# Pure_Keys_aec-pcb3.net
KiCad netlist of a schematic drawn in EAGLE
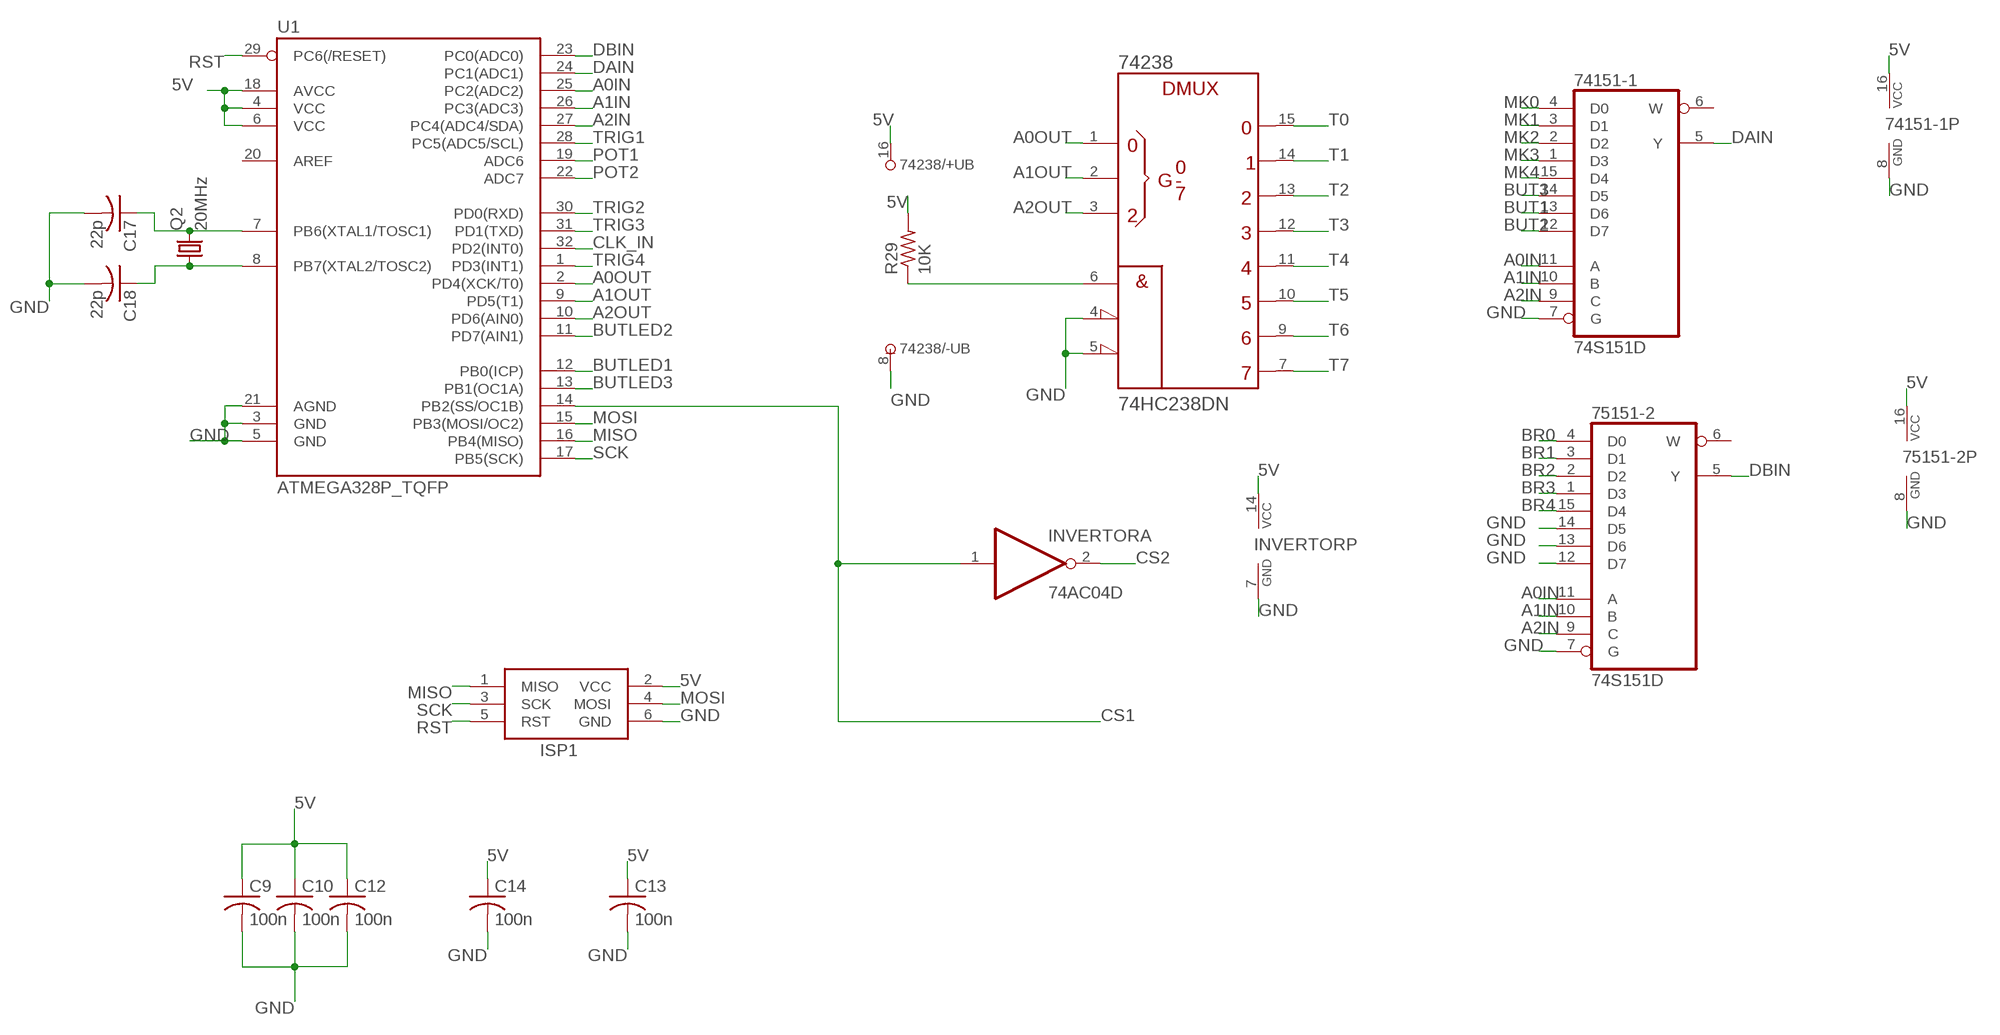
[diagram p0: schematic, sheet 1]
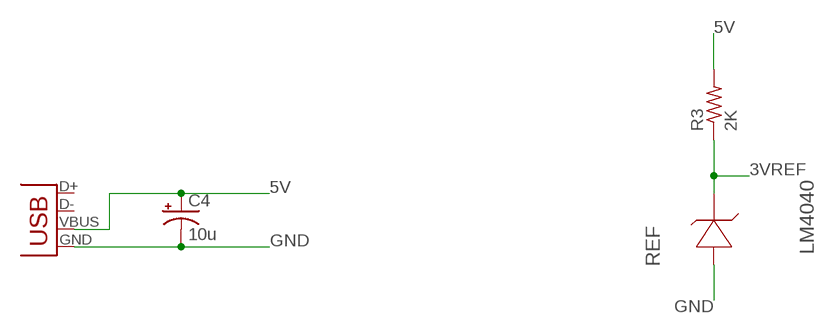
[diagram p1: schematic, sheet 2]
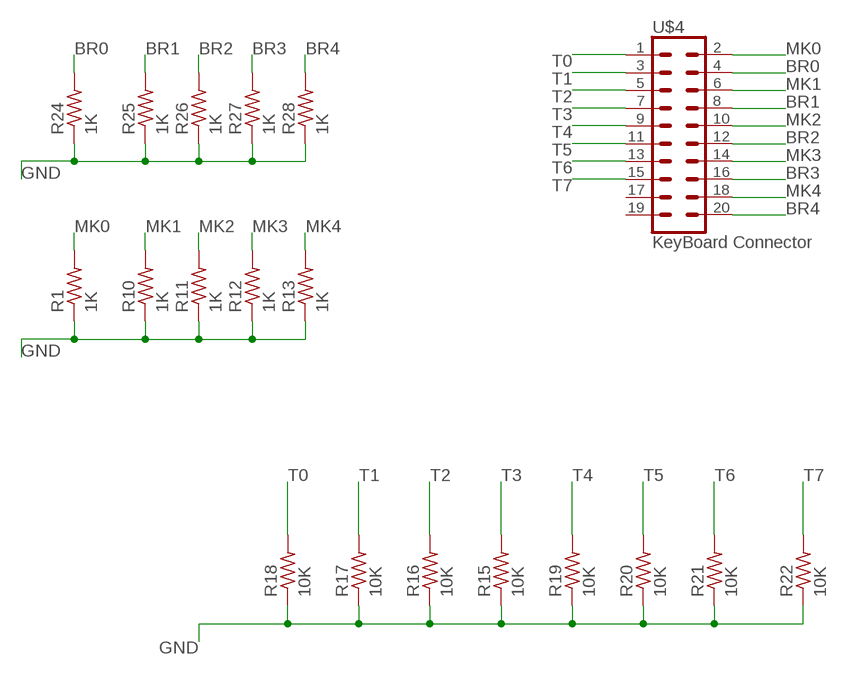
[diagram p2: schematic, sheet 3]
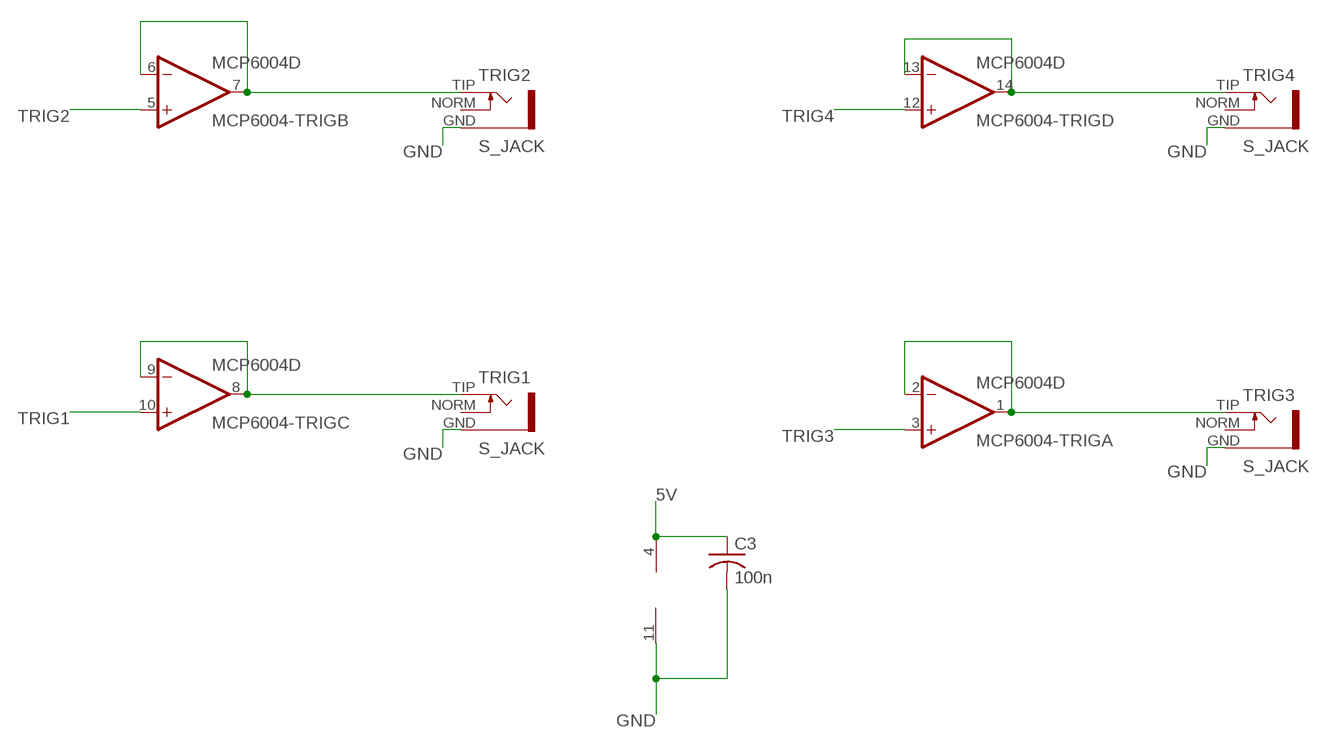
[diagram p3: schematic, sheet 4]
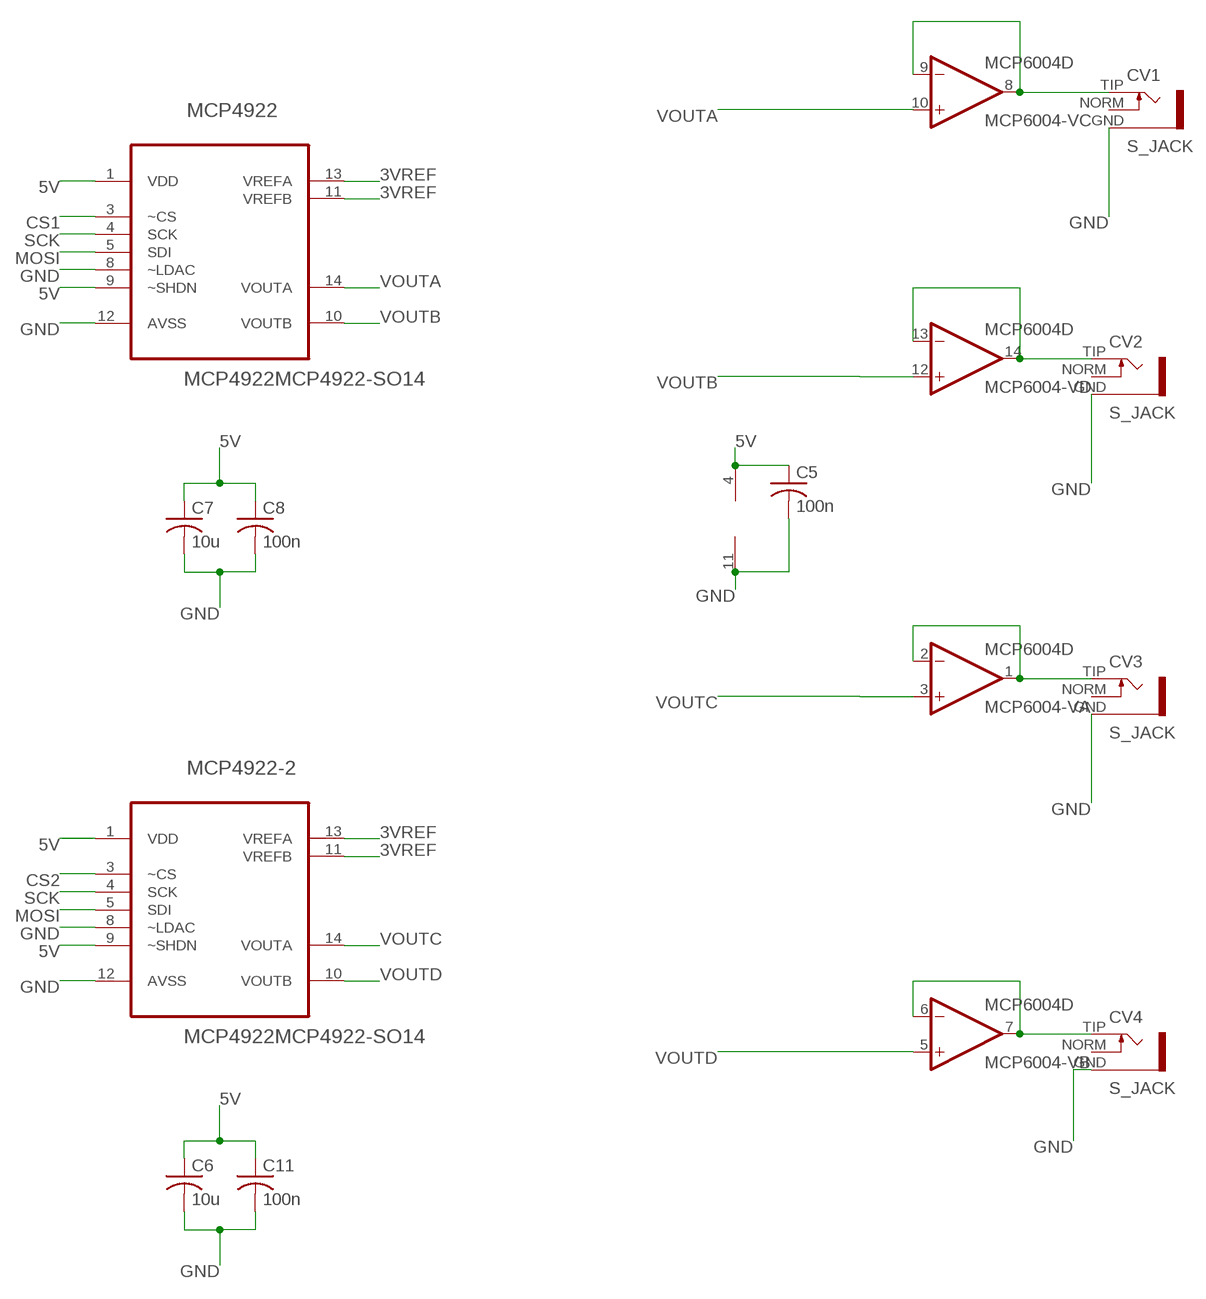
[diagram p4: schematic, sheet 5]
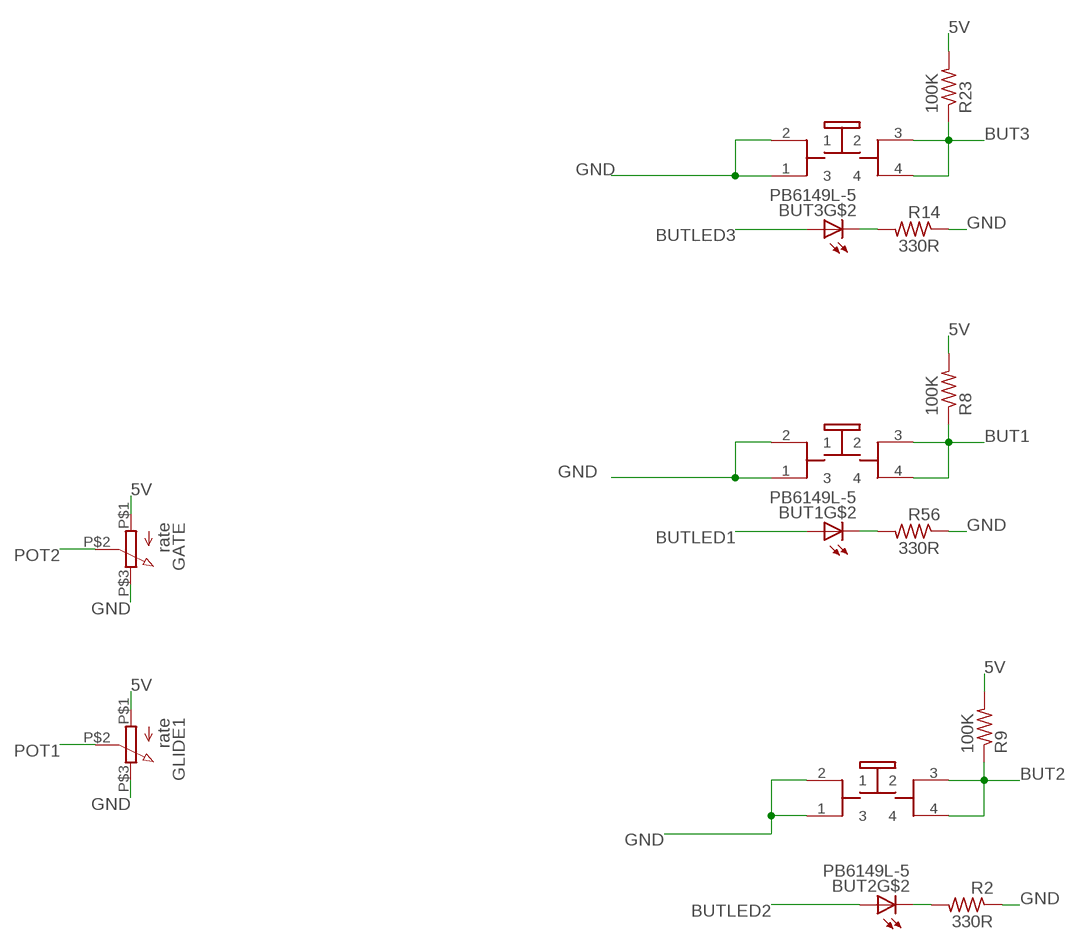
[diagram p5: schematic, sheet 6]
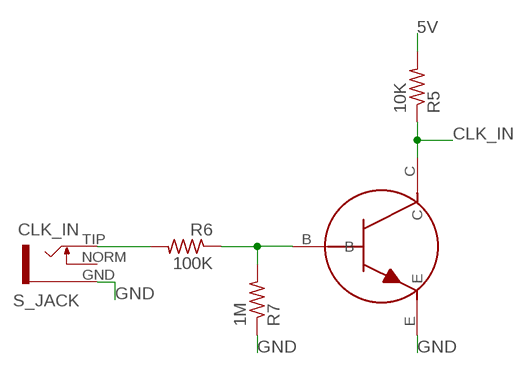
[diagram p6: schematic, sheet 7]

(export (version "E")
  (design (tool "Eeschema 10.0.6"))
  (components
    (comp (ref "CLK_IN")
      (value "S_JACK")
      (footprint "eagle-import:S_JACK")
      (libsource (lib "eagle-import") (part "S_JACK"))
    )
    (comp (ref "CLOCK")
      (value "2N3904")
      (footprint "eagle-import:TRANSISTOR_SINGLE_N-TYPE")
      (fields (field (name "RS-PART") "725-8616 "))
      (libsource (lib "eagle-import") (part "TRANSISTOR_MMBT3904"))
    )
    (comp (ref "R5")
      (value "10K")
      (footprint "eagle-import:R0805")
      (libsource (lib "eagle-import") (part "R-US_R0805"))
    )
    (comp (ref "R6")
      (value "100K")
      (footprint "eagle-import:R0805")
      (libsource (lib "eagle-import") (part "R-US_R0805"))
    )
    (comp (ref "R7")
      (value "1M")
      (footprint "eagle-import:R0805")
      (libsource (lib "eagle-import") (part "R-US_R0805"))
    )
    (comp (ref "74151-1")
      (value "74S151D")
      (footprint "eagle-import:SO16")
      (fields (field (name "RS-PART") "436-7436"))
      (libsource (lib "eagle-import") (part "74151DS"))
    )
    (comp (ref "74238")
      (value "74HC238DN")
      (footprint "eagle-import:SO16")
      (fields (field (name "RS-PART") "483-6487 (10off)"))
      (libsource (lib "eagle-import") (part "74HC238DN"))
    )
    (comp (ref "75151-2")
      (value "74S151D")
      (footprint "eagle-import:SO16")
      (fields (field (name "RS-PART") "436-7436"))
      (libsource (lib "eagle-import") (part "74151DS"))
    )
    (comp (ref "C9")
      (value "100n")
      (footprint "eagle-import:C0805K")
      (libsource (lib "eagle-import") (part "C-USC0805K"))
    )
    (comp (ref "C10")
      (value "100n")
      (footprint "eagle-import:C0805K")
      (libsource (lib "eagle-import") (part "C-USC0805K"))
    )
    (comp (ref "C12")
      (value "100n")
      (footprint "eagle-import:C0805K")
      (libsource (lib "eagle-import") (part "C-USC0805K"))
    )
    (comp (ref "C13")
      (value "100n")
      (footprint "eagle-import:C0805K")
      (libsource (lib "eagle-import") (part "C-USC0805K"))
    )
    (comp (ref "C14")
      (value "100n")
      (footprint "eagle-import:C0805K")
      (libsource (lib "eagle-import") (part "C-USC0805K"))
    )
    (comp (ref "C17")
      (value "22p")
      (footprint "eagle-import:C0805K")
      (libsource (lib "eagle-import") (part "C-USC0805K"))
    )
    (comp (ref "C18")
      (value "22p")
      (footprint "eagle-import:C0805K")
      (libsource (lib "eagle-import") (part "C-USC0805K"))
    )
    (comp (ref "INVERTOR")
      (value "74AC04D")
      (footprint "eagle-import:SO14")
      (fields (field (name "RS-PART") "171-3461 (50 off)"))
      (libsource (lib "eagle-import") (part "7404DAC"))
    )
    (comp (ref "ISP1")
      (value "AVRISP-6")
      (footprint "eagle-import:AVRISP")
      (libsource (lib "eagle-import") (part "AVRISP-6"))
    )
    (comp (ref "Q2")
      (value "20MHz")
      (footprint "eagle-import:HC49UP")
      (libsource (lib "eagle-import") (part "CRYSTALHC49UP"))
    )
    (comp (ref "R29")
      (value "10K")
      (footprint "eagle-import:R0805")
      (libsource (lib "eagle-import") (part "R-US_R0805"))
    )
    (comp (ref "U1")
      (value "ATMEGA328P_TQFP")
      (footprint "eagle-import:TQFP32-08")
      (fields (field (name "RS-PART") "131-0271"))
      (libsource (lib "eagle-import") (part "ATMEGA328P_TQFP"))
    )
    (comp (ref "C3")
      (value "100n")
      (footprint "eagle-import:C0805K")
      (libsource (lib "eagle-import") (part "C-USC0805K"))
    )
    (comp (ref "MCP6004-TRIG")
      (value "MCP6004D")
      (footprint "eagle-import:SO14")
      (fields (field (name "RS-PART") "628-3481 (10)"))
      (libsource (lib "eagle-import") (part "MCP6004D"))
    )
    (comp (ref "TRIG1")
      (value "S_JACK")
      (footprint "eagle-import:S_JACK")
      (libsource (lib "eagle-import") (part "S_JACK"))
    )
    (comp (ref "TRIG2")
      (value "S_JACK")
      (footprint "eagle-import:S_JACK")
      (libsource (lib "eagle-import") (part "S_JACK"))
    )
    (comp (ref "TRIG3")
      (value "S_JACK")
      (footprint "eagle-import:S_JACK")
      (libsource (lib "eagle-import") (part "S_JACK"))
    )
    (comp (ref "TRIG4")
      (value "S_JACK")
      (footprint "eagle-import:S_JACK")
      (libsource (lib "eagle-import") (part "S_JACK"))
    )
    (comp (ref "C5")
      (value "100n")
      (footprint "eagle-import:C0805K")
      (libsource (lib "eagle-import") (part "C-USC0805K"))
    )
    (comp (ref "C6")
      (value "10u")
      (footprint "eagle-import:C0805K")
      (libsource (lib "eagle-import") (part "C-USC0805K"))
    )
    (comp (ref "C7")
      (value "10u")
      (footprint "eagle-import:C0805K")
      (libsource (lib "eagle-import") (part "C-USC0805K"))
    )
    (comp (ref "C8")
      (value "100n")
      (footprint "eagle-import:C0805K")
      (libsource (lib "eagle-import") (part "C-USC0805K"))
    )
    (comp (ref "C11")
      (value "100n")
      (footprint "eagle-import:C0805K")
      (libsource (lib "eagle-import") (part "C-USC0805K"))
    )
    (comp (ref "CV1")
      (value "S_JACK")
      (footprint "eagle-import:S_JACK")
      (libsource (lib "eagle-import") (part "S_JACK"))
    )
    (comp (ref "CV2")
      (value "S_JACK")
      (footprint "eagle-import:S_JACK")
      (libsource (lib "eagle-import") (part "S_JACK"))
    )
    (comp (ref "CV3")
      (value "S_JACK")
      (footprint "eagle-import:S_JACK")
      (libsource (lib "eagle-import") (part "S_JACK"))
    )
    (comp (ref "CV4")
      (value "S_JACK")
      (footprint "eagle-import:S_JACK")
      (libsource (lib "eagle-import") (part "S_JACK"))
    )
    (comp (ref "MCP4922")
      (value "MCP4922MCP4922-SO14")
      (footprint "eagle-import:SO14")
      (fields (field (name "RS-PART") "402-910 "))
      (libsource (lib "eagle-import") (part "MCP4922MCP4922-SO14"))
    )
    (comp (ref "MCP4922-2")
      (value "MCP4922MCP4922-SO14")
      (footprint "eagle-import:SO14")
      (libsource (lib "eagle-import") (part "MCP4922MCP4922-SO14"))
    )
    (comp (ref "MCP6004-V")
      (value "MCP6004D")
      (footprint "eagle-import:SO14")
      (fields (field (name "RS-PART") "628-3481 (10)"))
      (libsource (lib "eagle-import") (part "MCP6004D"))
    )
    (comp (ref "R1")
      (value "1K")
      (footprint "eagle-import:R0805")
      (fields (field (name "RS-PART") "223-0427"))
      (libsource (lib "eagle-import") (part "R-US_R0805"))
    )
    (comp (ref "R10")
      (value "1K")
      (footprint "eagle-import:R0805")
      (fields (field (name "RS-PART") "223-0427"))
      (libsource (lib "eagle-import") (part "R-US_R0805"))
    )
    (comp (ref "R11")
      (value "1K")
      (footprint "eagle-import:R0805")
      (fields (field (name "RS-PART") "223-0427"))
      (libsource (lib "eagle-import") (part "R-US_R0805"))
    )
    (comp (ref "R12")
      (value "1K")
      (footprint "eagle-import:R0805")
      (fields (field (name "RS-PART") "223-0427"))
      (libsource (lib "eagle-import") (part "R-US_R0805"))
    )
    (comp (ref "R13")
      (value "1K")
      (footprint "eagle-import:R0805")
      (fields (field (name "RS-PART") "223-0427"))
      (libsource (lib "eagle-import") (part "R-US_R0805"))
    )
    (comp (ref "R15")
      (value "10K")
      (footprint "eagle-import:R0805")
      (libsource (lib "eagle-import") (part "R-US_R0805"))
    )
    (comp (ref "R16")
      (value "10K")
      (footprint "eagle-import:R0805")
      (libsource (lib "eagle-import") (part "R-US_R0805"))
    )
    (comp (ref "R17")
      (value "10K")
      (footprint "eagle-import:R0805")
      (libsource (lib "eagle-import") (part "R-US_R0805"))
    )
    (comp (ref "R18")
      (value "10K")
      (footprint "eagle-import:R0805")
      (libsource (lib "eagle-import") (part "R-US_R0805"))
    )
    (comp (ref "R19")
      (value "10K")
      (footprint "eagle-import:R0805")
      (libsource (lib "eagle-import") (part "R-US_R0805"))
    )
    (comp (ref "R20")
      (value "10K")
      (footprint "eagle-import:R0805")
      (libsource (lib "eagle-import") (part "R-US_R0805"))
    )
    (comp (ref "R21")
      (value "10K")
      (footprint "eagle-import:R0805")
      (libsource (lib "eagle-import") (part "R-US_R0805"))
    )
    (comp (ref "R22")
      (value "10K")
      (footprint "eagle-import:R0805")
      (libsource (lib "eagle-import") (part "R-US_R0805"))
    )
    (comp (ref "R24")
      (value "1K")
      (footprint "eagle-import:R0805")
      (fields (field (name "RS-PART") "223-0427"))
      (libsource (lib "eagle-import") (part "R-US_R0805"))
    )
    (comp (ref "R25")
      (value "1K")
      (footprint "eagle-import:R0805")
      (fields (field (name "RS-PART") "223-0427"))
      (libsource (lib "eagle-import") (part "R-US_R0805"))
    )
    (comp (ref "R26")
      (value "1K")
      (footprint "eagle-import:R0805")
      (fields (field (name "RS-PART") "223-0427"))
      (libsource (lib "eagle-import") (part "R-US_R0805"))
    )
    (comp (ref "R27")
      (value "1K")
      (footprint "eagle-import:R0805")
      (fields (field (name "RS-PART") "223-0427"))
      (libsource (lib "eagle-import") (part "R-US_R0805"))
    )
    (comp (ref "R28")
      (value "1K")
      (footprint "eagle-import:R0805")
      (fields (field (name "RS-PART") "223-0427"))
      (libsource (lib "eagle-import") (part "R-US_R0805"))
    )
    (comp (ref "U$4")
      (value "KeyBoard Connector")
      (footprint "eagle-import:2X10")
      (fields (field (name "RS-PART") "669-5364"))
      (libsource (lib "eagle-import") (part "CONN_10X2"))
    )
    (comp (ref "C4")
      (value "10u")
      (footprint "eagle-import:153CLV-0505")
      (libsource (lib "eagle-import") (part "CPOL-US153CLV-0505"))
    )
    (comp (ref "JP2")
      (value "USB-B")
      (footprint "eagle-import:USB-B-PTH")
      (libsource (lib "eagle-import") (part "USBPTH"))
    )
    (comp (ref "R3")
      (value "2K")
      (footprint "eagle-import:R0805")
      (libsource (lib "eagle-import") (part "R-US_R0805"))
    )
    (comp (ref "REF")
      (value "LM4040")
      (footprint "eagle-import:SOT95P237X112-3N")
      (fields
        (field (name "MPN") "LM4040A50IDBZT")
        (field (name "MPN_1") "LM4040A30IDBZT")
        (field (name "RS-PART") "809-6343")
      )
      (libsource (lib "eagle-import") (part "LM4040A30IDBZT"))
    )
    (comp (ref "BUT1")
      (value "PB6149L-5")
      (footprint "eagle-import:PB6149L")
      (libsource (lib "eagle-import") (part "PB6149L-5"))
    )
    (comp (ref "BUT2")
      (value "PB6149L-5")
      (footprint "eagle-import:PB6149L")
      (libsource (lib "eagle-import") (part "PB6149L-5"))
    )
    (comp (ref "BUT3")
      (value "PB6149L-5")
      (footprint "eagle-import:PB6149L")
      (libsource (lib "eagle-import") (part "PB6149L-5"))
    )
    (comp (ref "GATE")
      (value "rate")
      (footprint "eagle-import:POT")
      (libsource (lib "eagle-import") (part "9MMPOT"))
    )
    (comp (ref "GLIDE1")
      (value "rate")
      (footprint "eagle-import:POT")
      (libsource (lib "eagle-import") (part "9MMPOT"))
    )
    (comp (ref "R2")
      (value "330R")
      (footprint "eagle-import:R0805")
      (libsource (lib "eagle-import") (part "R-US_R0805"))
    )
    (comp (ref "R8")
      (value "100K")
      (footprint "eagle-import:R0805")
      (libsource (lib "eagle-import") (part "R-US_R0805"))
    )
    (comp (ref "R9")
      (value "100K")
      (footprint "eagle-import:R0805")
      (libsource (lib "eagle-import") (part "R-US_R0805"))
    )
    (comp (ref "R14")
      (value "330R")
      (footprint "eagle-import:R0805")
      (libsource (lib "eagle-import") (part "R-US_R0805"))
    )
    (comp (ref "R23")
      (value "100K")
      (footprint "eagle-import:R0805")
      (libsource (lib "eagle-import") (part "R-US_R0805"))
    )
    (comp (ref "R56")
      (value "330R")
      (footprint "eagle-import:R0805")
      (libsource (lib "eagle-import") (part "R-US_R0805"))
    )
  )
  (nets
    (net (code "1") (name "3VREF") (class "Default")
      (node (ref "MCP4922") (pin "11") (pinfunction "VREFB_11") (pintype "bidirectional"))
      (node (ref "MCP4922") (pin "13") (pinfunction "VREFA_13") (pintype "input"))
      (node (ref "MCP4922-2") (pin "11") (pinfunction "VREFB_11") (pintype "bidirectional"))
      (node (ref "MCP4922-2") (pin "13") (pinfunction "VREFA_13") (pintype "input"))
      (node (ref "R3") (pin "1") (pinfunction "1_1") (pintype "passive"))
      (node (ref "REF") (pin "1") (pinfunction "CATHODE_1") (pintype "output"))
    )
    (net (code "2") (name "5V") (class "Default")
      (node (ref "74151-1") (pin "16") (pinfunction "VCC_16") (pintype "power_in"))
      (node (ref "74238") (pin "16") (pinfunction "+UB_16") (pintype "power_in"))
      (node (ref "75151-2") (pin "16") (pinfunction "VCC_16") (pintype "power_in"))
      (node (ref "C10") (pin "1") (pinfunction "1_1") (pintype "passive"))
      (node (ref "C11") (pin "1") (pinfunction "1_1") (pintype "passive"))
      (node (ref "C12") (pin "1") (pinfunction "1_1") (pintype "passive"))
      (node (ref "C13") (pin "1") (pinfunction "1_1") (pintype "passive"))
      (node (ref "C14") (pin "1") (pinfunction "1_1") (pintype "passive"))
      (node (ref "C3") (pin "1") (pinfunction "1_1") (pintype "passive"))
      (node (ref "C4") (pin "+") (pinfunction "+_+") (pintype "passive"))
      (node (ref "C5") (pin "1") (pinfunction "1_1") (pintype "passive"))
      (node (ref "C6") (pin "1") (pinfunction "1_1") (pintype "passive"))
      (node (ref "C7") (pin "1") (pinfunction "1_1") (pintype "passive"))
      (node (ref "C8") (pin "1") (pinfunction "1_1") (pintype "passive"))
      (node (ref "C9") (pin "1") (pinfunction "1_1") (pintype "passive"))
      (node (ref "GATE") (pin "P$1") (pinfunction "1_P$1") (pintype "passive"))
      (node (ref "GLIDE1") (pin "P$1") (pinfunction "1_P$1") (pintype "passive"))
      (node (ref "INVERTOR") (pin "14") (pinfunction "VCC_14") (pintype "power_in"))
      (node (ref "ISP1") (pin "2") (pinfunction "VCC_2") (pintype "power_in"))
      (node (ref "JP2") (pin "VBUS") (pinfunction "VBUS_VBUS") (pintype "bidirectional"))
      (node (ref "MCP4922") (pin "1") (pinfunction "VDD_1") (pintype "power_in"))
      (node (ref "MCP4922") (pin "9") (pinfunction "~{SHDN}_9") (pintype "bidirectional"))
      (node (ref "MCP4922-2") (pin "1") (pinfunction "VDD_1") (pintype "power_in"))
      (node (ref "MCP4922-2") (pin "9") (pinfunction "~{SHDN}_9") (pintype "bidirectional"))
      (node (ref "MCP6004-TRIG") (pin "4") (pinfunction "V+_4") (pintype "power_in"))
      (node (ref "MCP6004-V") (pin "4") (pinfunction "V+_4") (pintype "power_in"))
      (node (ref "R23") (pin "2") (pinfunction "2_2") (pintype "passive"))
      (node (ref "R29") (pin "2") (pinfunction "2_2") (pintype "passive"))
      (node (ref "R3") (pin "2") (pinfunction "2_2") (pintype "passive"))
      (node (ref "R5") (pin "2") (pinfunction "2_2") (pintype "passive"))
      (node (ref "R8") (pin "2") (pinfunction "2_2") (pintype "passive"))
      (node (ref "R9") (pin "2") (pinfunction "2_2") (pintype "passive"))
      (node (ref "U1") (pin "18") (pinfunction "AVCC_18") (pintype "bidirectional"))
      (node (ref "U1") (pin "4") (pinfunction "VCC_4") (pintype "bidirectional"))
      (node (ref "U1") (pin "6") (pinfunction "VCC_6") (pintype "bidirectional"))
    )
    (net (code "3") (name "A0IN") (class "Default")
      (node (ref "74151-1") (pin "11") (pinfunction "A_11") (pintype "input"))
      (node (ref "75151-2") (pin "11") (pinfunction "A_11") (pintype "input"))
      (node (ref "U1") (pin "25") (pinfunction "PC2(ADC2)_25") (pintype "bidirectional"))
    )
    (net (code "4") (name "A0OUT") (class "Default")
      (node (ref "74238") (pin "1") (pinfunction "A_1") (pintype "input"))
      (node (ref "U1") (pin "2") (pinfunction "PD4(XCK/T0)_2") (pintype "bidirectional"))
    )
    (net (code "5") (name "A1IN") (class "Default")
      (node (ref "74151-1") (pin "10") (pinfunction "B_10") (pintype "input"))
      (node (ref "75151-2") (pin "10") (pinfunction "B_10") (pintype "input"))
      (node (ref "U1") (pin "26") (pinfunction "PC3(ADC3)_26") (pintype "bidirectional"))
    )
    (net (code "6") (name "A1OUT") (class "Default")
      (node (ref "74238") (pin "2") (pinfunction "B_2") (pintype "input"))
      (node (ref "U1") (pin "9") (pinfunction "PD5(T1)_9") (pintype "bidirectional"))
    )
    (net (code "7") (name "A2IN") (class "Default")
      (node (ref "74151-1") (pin "9") (pinfunction "C_9") (pintype "input"))
      (node (ref "75151-2") (pin "9") (pinfunction "C_9") (pintype "input"))
      (node (ref "U1") (pin "27") (pinfunction "PC4(ADC4/SDA)_27") (pintype "bidirectional"))
    )
    (net (code "8") (name "A2OUT") (class "Default")
      (node (ref "74238") (pin "3") (pinfunction "C_3") (pintype "input"))
      (node (ref "U1") (pin "10") (pinfunction "PD6(AIN0)_10") (pintype "bidirectional"))
    )
    (net (code "9") (name "BR0") (class "Default")
      (node (ref "75151-2") (pin "4") (pinfunction "D0_4") (pintype "input"))
      (node (ref "R24") (pin "2") (pinfunction "2_2") (pintype "passive"))
      (node (ref "U$4") (pin "4") (pinfunction "4_4") (pintype "passive"))
    )
    (net (code "10") (name "BR1") (class "Default")
      (node (ref "75151-2") (pin "3") (pinfunction "D1_3") (pintype "input"))
      (node (ref "R25") (pin "2") (pinfunction "2_2") (pintype "passive"))
      (node (ref "U$4") (pin "8") (pinfunction "8_8") (pintype "passive"))
    )
    (net (code "11") (name "BR2") (class "Default")
      (node (ref "75151-2") (pin "2") (pinfunction "D2_2") (pintype "input"))
      (node (ref "R26") (pin "2") (pinfunction "2_2") (pintype "passive"))
      (node (ref "U$4") (pin "12") (pinfunction "12_12") (pintype "passive"))
    )
    (net (code "12") (name "BR3") (class "Default")
      (node (ref "75151-2") (pin "1") (pinfunction "D3_1") (pintype "input"))
      (node (ref "R27") (pin "2") (pinfunction "2_2") (pintype "passive"))
      (node (ref "U$4") (pin "16") (pinfunction "16_16") (pintype "passive"))
    )
    (net (code "13") (name "BR4") (class "Default")
      (node (ref "75151-2") (pin "15") (pinfunction "D4_15") (pintype "input"))
      (node (ref "R28") (pin "2") (pinfunction "2_2") (pintype "passive"))
      (node (ref "U$4") (pin "20") (pinfunction "20_20") (pintype "passive"))
    )
    (net (code "14") (name "BUT1") (class "Default")
      (node (ref "74151-1") (pin "13") (pinfunction "D6_13") (pintype "input"))
      (node (ref "BUT1") (pin "3") (pinfunction "2_3") (pintype "bidirectional"))
      (node (ref "BUT1") (pin "4") (pinfunction "4_4") (pintype "bidirectional"))
      (node (ref "R8") (pin "1") (pinfunction "1_1") (pintype "passive"))
    )
    (net (code "15") (name "BUT2") (class "Default")
      (node (ref "74151-1") (pin "12") (pinfunction "D7_12") (pintype "input"))
      (node (ref "BUT2") (pin "3") (pinfunction "2_3") (pintype "bidirectional"))
      (node (ref "BUT2") (pin "4") (pinfunction "4_4") (pintype "bidirectional"))
      (node (ref "R9") (pin "1") (pinfunction "1_1") (pintype "passive"))
    )
    (net (code "16") (name "BUT3") (class "Default")
      (node (ref "74151-1") (pin "14") (pinfunction "D5_14") (pintype "input"))
      (node (ref "BUT3") (pin "3") (pinfunction "2_3") (pintype "bidirectional"))
      (node (ref "BUT3") (pin "4") (pinfunction "4_4") (pintype "bidirectional"))
      (node (ref "R23") (pin "1") (pinfunction "1_1") (pintype "passive"))
    )
    (net (code "17") (name "BUTLED1") (class "Default")
      (node (ref "BUT1") (pin "A") (pinfunction "A_A") (pintype "passive"))
      (node (ref "U1") (pin "12") (pinfunction "PB0(ICP)_12") (pintype "bidirectional"))
    )
    (net (code "18") (name "BUTLED2") (class "Default")
      (node (ref "BUT2") (pin "A") (pinfunction "A_A") (pintype "passive"))
      (node (ref "U1") (pin "11") (pinfunction "PD7(AIN1)_11") (pintype "bidirectional"))
    )
    (net (code "19") (name "BUTLED3") (class "Default")
      (node (ref "BUT3") (pin "A") (pinfunction "A_A") (pintype "passive"))
      (node (ref "U1") (pin "13") (pinfunction "PB1(OC1A)_13") (pintype "bidirectional"))
    )
    (net (code "20") (name "CLK_IN") (class "Default")
      (node (ref "CLOCK") (pin "C") (pinfunction "C_C") (pintype "bidirectional"))
      (node (ref "R5") (pin "1") (pinfunction "1_1") (pintype "passive"))
      (node (ref "U1") (pin "32") (pinfunction "PD2(INT0)_32") (pintype "bidirectional"))
    )
    (net (code "21") (name "CS1") (class "Default")
      (node (ref "INVERTOR") (pin "1") (pinfunction "I_1") (pintype "input"))
      (node (ref "MCP4922") (pin "3") (pinfunction "~{CS}_3") (pintype "input"))
      (node (ref "U1") (pin "14") (pinfunction "PB2(SS/OC1B)_14") (pintype "bidirectional"))
    )
    (net (code "22") (name "CS2") (class "Default")
      (node (ref "INVERTOR") (pin "2") (pinfunction "O_2") (pintype "output"))
      (node (ref "MCP4922-2") (pin "3") (pinfunction "~{CS}_3") (pintype "input"))
    )
    (net (code "23") (name "DAIN") (class "Default")
      (node (ref "74151-1") (pin "5") (pinfunction "Y_5") (pintype "output"))
      (node (ref "U1") (pin "24") (pinfunction "PC1(ADC1)_24") (pintype "bidirectional"))
    )
    (net (code "24") (name "DBIN") (class "Default")
      (node (ref "75151-2") (pin "5") (pinfunction "Y_5") (pintype "output"))
      (node (ref "U1") (pin "23") (pinfunction "PC0(ADC0)_23") (pintype "bidirectional"))
    )
    (net (code "25") (name "GND") (class "Default")
      (node (ref "74151-1") (pin "7") (pinfunction "G_7") (pintype "input"))
      (node (ref "74151-1") (pin "8") (pinfunction "GND_8") (pintype "power_in"))
      (node (ref "74238") (pin "4") (pinfunction "~{G2A}_4") (pintype "input"))
      (node (ref "74238") (pin "5") (pinfunction "~{G2B}_5") (pintype "input"))
      (node (ref "74238") (pin "8") (pinfunction "-UB_8") (pintype "power_in"))
      (node (ref "75151-2") (pin "12") (pinfunction "D7_12") (pintype "input"))
      (node (ref "75151-2") (pin "13") (pinfunction "D6_13") (pintype "input"))
      (node (ref "75151-2") (pin "14") (pinfunction "D5_14") (pintype "input"))
      (node (ref "75151-2") (pin "7") (pinfunction "G_7") (pintype "input"))
      (node (ref "75151-2") (pin "8") (pinfunction "GND_8") (pintype "power_in"))
      (node (ref "BUT1") (pin "1") (pinfunction "3_1") (pintype "bidirectional"))
      (node (ref "BUT1") (pin "2") (pinfunction "1_2") (pintype "bidirectional"))
      (node (ref "BUT2") (pin "1") (pinfunction "3_1") (pintype "bidirectional"))
      (node (ref "BUT2") (pin "2") (pinfunction "1_2") (pintype "bidirectional"))
      (node (ref "BUT3") (pin "1") (pinfunction "3_1") (pintype "bidirectional"))
      (node (ref "BUT3") (pin "2") (pinfunction "1_2") (pintype "bidirectional"))
      (node (ref "C10") (pin "2") (pinfunction "2_2") (pintype "passive"))
      (node (ref "C11") (pin "2") (pinfunction "2_2") (pintype "passive"))
      (node (ref "C12") (pin "2") (pinfunction "2_2") (pintype "passive"))
      (node (ref "C13") (pin "2") (pinfunction "2_2") (pintype "passive"))
      (node (ref "C14") (pin "2") (pinfunction "2_2") (pintype "passive"))
      (node (ref "C17") (pin "2") (pinfunction "2_2") (pintype "passive"))
      (node (ref "C18") (pin "2") (pinfunction "2_2") (pintype "passive"))
      (node (ref "C3") (pin "2") (pinfunction "2_2") (pintype "passive"))
      (node (ref "C4") (pin "-") (pinfunction "-_-") (pintype "passive"))
      (node (ref "C5") (pin "2") (pinfunction "2_2") (pintype "passive"))
      (node (ref "C6") (pin "2") (pinfunction "2_2") (pintype "passive"))
      (node (ref "C7") (pin "2") (pinfunction "2_2") (pintype "passive"))
      (node (ref "C8") (pin "2") (pinfunction "2_2") (pintype "passive"))
      (node (ref "C9") (pin "2") (pinfunction "2_2") (pintype "passive"))
      (node (ref "CLK_IN") (pin "GND") (pinfunction "GND_GND") (pintype "passive"))
      (node (ref "CLOCK") (pin "E") (pinfunction "E_E") (pintype "bidirectional"))
      (node (ref "CV1") (pin "GND") (pinfunction "GND_GND") (pintype "passive"))
      (node (ref "CV2") (pin "GND") (pinfunction "GND_GND") (pintype "passive"))
      (node (ref "CV3") (pin "GND") (pinfunction "GND_GND") (pintype "passive"))
      (node (ref "CV4") (pin "GND") (pinfunction "GND_GND") (pintype "passive"))
      (node (ref "GATE") (pin "P$3") (pinfunction "3_P$3") (pintype "passive"))
      (node (ref "GLIDE1") (pin "P$3") (pinfunction "3_P$3") (pintype "passive"))
      (node (ref "INVERTOR") (pin "7") (pinfunction "GND_7") (pintype "power_in"))
      (node (ref "ISP1") (pin "6") (pinfunction "GND_6") (pintype "power_in"))
      (node (ref "JP2") (pin "GND") (pinfunction "GND_GND") (pintype "bidirectional"))
      (node (ref "MCP4922") (pin "12") (pinfunction "AVSS_12") (pintype "passive"))
      (node (ref "MCP4922") (pin "8") (pinfunction "~{LDAC}_8") (pintype "input"))
      (node (ref "MCP4922-2") (pin "12") (pinfunction "AVSS_12") (pintype "passive"))
      (node (ref "MCP4922-2") (pin "8") (pinfunction "~{LDAC}_8") (pintype "input"))
      (node (ref "MCP6004-TRIG") (pin "11") (pinfunction "V-_11") (pintype "power_in"))
      (node (ref "MCP6004-V") (pin "11") (pinfunction "V-_11") (pintype "power_in"))
      (node (ref "R1") (pin "1") (pinfunction "1_1") (pintype "passive"))
      (node (ref "R10") (pin "1") (pinfunction "1_1") (pintype "passive"))
      (node (ref "R11") (pin "1") (pinfunction "1_1") (pintype "passive"))
      (node (ref "R12") (pin "1") (pinfunction "1_1") (pintype "passive"))
      (node (ref "R13") (pin "1") (pinfunction "1_1") (pintype "passive"))
      (node (ref "R14") (pin "1") (pinfunction "1_1") (pintype "passive"))
      (node (ref "R15") (pin "1") (pinfunction "1_1") (pintype "passive"))
      (node (ref "R16") (pin "1") (pinfunction "1_1") (pintype "passive"))
      (node (ref "R17") (pin "1") (pinfunction "1_1") (pintype "passive"))
      (node (ref "R18") (pin "1") (pinfunction "1_1") (pintype "passive"))
      (node (ref "R19") (pin "1") (pinfunction "1_1") (pintype "passive"))
      (node (ref "R2") (pin "1") (pinfunction "1_1") (pintype "passive"))
      (node (ref "R20") (pin "1") (pinfunction "1_1") (pintype "passive"))
      (node (ref "R21") (pin "1") (pinfunction "1_1") (pintype "passive"))
      (node (ref "R22") (pin "1") (pinfunction "1_1") (pintype "passive"))
      (node (ref "R24") (pin "1") (pinfunction "1_1") (pintype "passive"))
      (node (ref "R25") (pin "1") (pinfunction "1_1") (pintype "passive"))
      (node (ref "R26") (pin "1") (pinfunction "1_1") (pintype "passive"))
      (node (ref "R27") (pin "1") (pinfunction "1_1") (pintype "passive"))
      (node (ref "R28") (pin "1") (pinfunction "1_1") (pintype "passive"))
      (node (ref "R56") (pin "1") (pinfunction "1_1") (pintype "passive"))
      (node (ref "R7") (pin "1") (pinfunction "1_1") (pintype "passive"))
      (node (ref "REF") (pin "2") (pinfunction "ANODE_2") (pintype "input"))
      (node (ref "TRIG1") (pin "GND") (pinfunction "GND_GND") (pintype "passive"))
      (node (ref "TRIG2") (pin "GND") (pinfunction "GND_GND") (pintype "passive"))
      (node (ref "TRIG3") (pin "GND") (pinfunction "GND_GND") (pintype "passive"))
      (node (ref "TRIG4") (pin "GND") (pinfunction "GND_GND") (pintype "passive"))
      (node (ref "U1") (pin "21") (pinfunction "AGND_21") (pintype "bidirectional"))
      (node (ref "U1") (pin "3") (pinfunction "GND_3") (pintype "bidirectional"))
      (node (ref "U1") (pin "5") (pinfunction "GND_5") (pintype "bidirectional"))
    )
    (net (code "26") (name "MISO") (class "Default")
      (node (ref "ISP1") (pin "1") (pinfunction "MISO_1") (pintype "input"))
      (node (ref "U1") (pin "16") (pinfunction "PB4(MISO)_16") (pintype "bidirectional"))
    )
    (net (code "27") (name "MK0") (class "Default")
      (node (ref "74151-1") (pin "4") (pinfunction "D0_4") (pintype "input"))
      (node (ref "R1") (pin "2") (pinfunction "2_2") (pintype "passive"))
      (node (ref "U$4") (pin "2") (pinfunction "2_2") (pintype "passive"))
    )
    (net (code "28") (name "MK1") (class "Default")
      (node (ref "74151-1") (pin "3") (pinfunction "D1_3") (pintype "input"))
      (node (ref "R10") (pin "2") (pinfunction "2_2") (pintype "passive"))
      (node (ref "U$4") (pin "6") (pinfunction "6_6") (pintype "passive"))
    )
    (net (code "29") (name "MK2") (class "Default")
      (node (ref "74151-1") (pin "2") (pinfunction "D2_2") (pintype "input"))
      (node (ref "R11") (pin "2") (pinfunction "2_2") (pintype "passive"))
      (node (ref "U$4") (pin "10") (pinfunction "10_10") (pintype "passive"))
    )
    (net (code "30") (name "MK3") (class "Default")
      (node (ref "74151-1") (pin "1") (pinfunction "D3_1") (pintype "input"))
      (node (ref "R12") (pin "2") (pinfunction "2_2") (pintype "passive"))
      (node (ref "U$4") (pin "14") (pinfunction "14_14") (pintype "passive"))
    )
    (net (code "31") (name "MK4") (class "Default")
      (node (ref "74151-1") (pin "15") (pinfunction "D4_15") (pintype "input"))
      (node (ref "R13") (pin "2") (pinfunction "2_2") (pintype "passive"))
      (node (ref "U$4") (pin "18") (pinfunction "18_18") (pintype "passive"))
    )
    (net (code "32") (name "MOSI") (class "Default")
      (node (ref "ISP1") (pin "4") (pinfunction "MOSI_4") (pintype "output"))
      (node (ref "MCP4922") (pin "5") (pinfunction "SDI_5") (pintype "input"))
      (node (ref "MCP4922-2") (pin "5") (pinfunction "SDI_5") (pintype "input"))
      (node (ref "U1") (pin "15") (pinfunction "PB3(MOSI/OC2)_15") (pintype "bidirectional"))
    )
    (net (code "33") (name "Net-(74238C-G1)") (class "Default")
      (node (ref "74238") (pin "6") (pinfunction "G1_6") (pintype "input"))
      (node (ref "R29") (pin "1") (pinfunction "1_1") (pintype "passive"))
    )
    (net (code "34") (name "Net-(BUT1B-C)") (class "Default")
      (node (ref "BUT1") (pin "K") (pinfunction "C_K") (pintype "passive"))
      (node (ref "R56") (pin "2") (pinfunction "2_2") (pintype "passive"))
    )
    (net (code "35") (name "Net-(BUT2B-C)") (class "Default")
      (node (ref "BUT2") (pin "K") (pinfunction "C_K") (pintype "passive"))
      (node (ref "R2") (pin "2") (pinfunction "2_2") (pintype "passive"))
    )
    (net (code "36") (name "Net-(BUT3B-C)") (class "Default")
      (node (ref "BUT3") (pin "K") (pinfunction "C_K") (pintype "passive"))
      (node (ref "R14") (pin "2") (pinfunction "2_2") (pintype "passive"))
    )
    (net (code "37") (name "Net-(CLK_IN-PadTIP)") (class "Default")
      (node (ref "CLK_IN") (pin "TIP") (pinfunction "TIP_TIP") (pintype "passive"))
      (node (ref "R6") (pin "2") (pinfunction "2_2") (pintype "passive"))
    )
    (net (code "38") (name "Net-(CLOCK-PadB)") (class "Default")
      (node (ref "CLOCK") (pin "B") (pinfunction "B_B") (pintype "bidirectional"))
      (node (ref "R6") (pin "1") (pinfunction "1_1") (pintype "passive"))
      (node (ref "R7") (pin "2") (pinfunction "2_2") (pintype "passive"))
    )
    (net (code "39") (name "Net-(MCP6004-TRIGA--IN)") (class "Default")
      (node (ref "MCP6004-TRIG") (pin "1") (pinfunction "OUT_1") (pintype "output"))
      (node (ref "MCP6004-TRIG") (pin "2") (pinfunction "-IN_2") (pintype "input"))
      (node (ref "TRIG3") (pin "TIP") (pinfunction "TIP_TIP") (pintype "passive"))
    )
    (net (code "40") (name "Net-(MCP6004-TRIGB--IN)") (class "Default")
      (node (ref "MCP6004-TRIG") (pin "6") (pinfunction "-IN_6") (pintype "input"))
      (node (ref "MCP6004-TRIG") (pin "7") (pinfunction "OUT_7") (pintype "output"))
      (node (ref "TRIG2") (pin "TIP") (pinfunction "TIP_TIP") (pintype "passive"))
    )
    (net (code "41") (name "Net-(MCP6004-TRIGC--IN)") (class "Default")
      (node (ref "MCP6004-TRIG") (pin "8") (pinfunction "OUT_8") (pintype "output"))
      (node (ref "MCP6004-TRIG") (pin "9") (pinfunction "-IN_9") (pintype "input"))
      (node (ref "TRIG1") (pin "TIP") (pinfunction "TIP_TIP") (pintype "passive"))
    )
    (net (code "42") (name "Net-(MCP6004-TRIGD--IN)") (class "Default")
      (node (ref "MCP6004-TRIG") (pin "13") (pinfunction "-IN_13") (pintype "input"))
      (node (ref "MCP6004-TRIG") (pin "14") (pinfunction "OUT_14") (pintype "output"))
      (node (ref "TRIG4") (pin "TIP") (pinfunction "TIP_TIP") (pintype "passive"))
    )
    (net (code "43") (name "Net-(MCP6004-VA--IN)") (class "Default")
      (node (ref "CV3") (pin "TIP") (pinfunction "TIP_TIP") (pintype "passive"))
      (node (ref "MCP6004-V") (pin "1") (pinfunction "OUT_1") (pintype "output"))
      (node (ref "MCP6004-V") (pin "2") (pinfunction "-IN_2") (pintype "input"))
    )
    (net (code "44") (name "Net-(MCP6004-VB--IN)") (class "Default")
      (node (ref "CV4") (pin "TIP") (pinfunction "TIP_TIP") (pintype "passive"))
      (node (ref "MCP6004-V") (pin "6") (pinfunction "-IN_6") (pintype "input"))
      (node (ref "MCP6004-V") (pin "7") (pinfunction "OUT_7") (pintype "output"))
    )
    (net (code "45") (name "Net-(MCP6004-VC--IN)") (class "Default")
      (node (ref "CV1") (pin "TIP") (pinfunction "TIP_TIP") (pintype "passive"))
      (node (ref "MCP6004-V") (pin "8") (pinfunction "OUT_8") (pintype "output"))
      (node (ref "MCP6004-V") (pin "9") (pinfunction "-IN_9") (pintype "input"))
    )
    (net (code "46") (name "Net-(MCP6004-VD--IN)") (class "Default")
      (node (ref "CV2") (pin "TIP") (pinfunction "TIP_TIP") (pintype "passive"))
      (node (ref "MCP6004-V") (pin "13") (pinfunction "-IN_13") (pintype "input"))
      (node (ref "MCP6004-V") (pin "14") (pinfunction "OUT_14") (pintype "output"))
    )
    (net (code "47") (name "Net-(U1-PB6(XTAL1{slash}TOSC1))") (class "Default")
      (node (ref "C17") (pin "1") (pinfunction "1_1") (pintype "passive"))
      (node (ref "Q2") (pin "2") (pinfunction "2_2") (pintype "passive"))
      (node (ref "U1") (pin "7") (pinfunction "PB6(XTAL1/TOSC1)_7") (pintype "bidirectional"))
    )
    (net (code "48") (name "Net-(U1-PB7(XTAL2{slash}TOSC2))") (class "Default")
      (node (ref "C18") (pin "1") (pinfunction "1_1") (pintype "passive"))
      (node (ref "Q2") (pin "1") (pinfunction "1_1") (pintype "passive"))
      (node (ref "U1") (pin "8") (pinfunction "PB7(XTAL2/TOSC2)_8") (pintype "bidirectional"))
    )
    (net (code "49") (name "POT1") (class "Default")
      (node (ref "GLIDE1") (pin "P$2") (pinfunction "2_P$2") (pintype "passive"))
      (node (ref "U1") (pin "19") (pinfunction "ADC6_19") (pintype "bidirectional"))
    )
    (net (code "50") (name "POT2") (class "Default")
      (node (ref "GATE") (pin "P$2") (pinfunction "2_P$2") (pintype "passive"))
      (node (ref "U1") (pin "22") (pinfunction "ADC7_22") (pintype "bidirectional"))
    )
    (net (code "51") (name "RST") (class "Default")
      (node (ref "ISP1") (pin "5") (pinfunction "RST_5") (pintype "output"))
      (node (ref "U1") (pin "29") (pinfunction "PC6(/RESET)_29") (pintype "bidirectional"))
    )
    (net (code "52") (name "SCK") (class "Default")
      (node (ref "ISP1") (pin "3") (pinfunction "SCK_3") (pintype "output"))
      (node (ref "MCP4922") (pin "4") (pinfunction "SCK_4") (pintype "input"))
      (node (ref "MCP4922-2") (pin "4") (pinfunction "SCK_4") (pintype "input"))
      (node (ref "U1") (pin "17") (pinfunction "PB5(SCK)_17") (pintype "bidirectional"))
    )
    (net (code "53") (name "T0") (class "Default")
      (node (ref "74238") (pin "15") (pinfunction "Y0_15") (pintype "output"))
      (node (ref "R18") (pin "2") (pinfunction "2_2") (pintype "passive"))
      (node (ref "U$4") (pin "1") (pinfunction "1_1") (pintype "passive"))
    )
    (net (code "54") (name "T1") (class "Default")
      (node (ref "74238") (pin "14") (pinfunction "Y1_14") (pintype "output"))
      (node (ref "R17") (pin "2") (pinfunction "2_2") (pintype "passive"))
      (node (ref "U$4") (pin "3") (pinfunction "3_3") (pintype "passive"))
    )
    (net (code "55") (name "T2") (class "Default")
      (node (ref "74238") (pin "13") (pinfunction "Y2_13") (pintype "output"))
      (node (ref "R16") (pin "2") (pinfunction "2_2") (pintype "passive"))
      (node (ref "U$4") (pin "5") (pinfunction "5_5") (pintype "passive"))
    )
    (net (code "56") (name "T3") (class "Default")
      (node (ref "74238") (pin "12") (pinfunction "Y3_12") (pintype "output"))
      (node (ref "R15") (pin "2") (pinfunction "2_2") (pintype "passive"))
      (node (ref "U$4") (pin "7") (pinfunction "7_7") (pintype "passive"))
    )
    (net (code "57") (name "T4") (class "Default")
      (node (ref "74238") (pin "11") (pinfunction "Y4_11") (pintype "output"))
      (node (ref "R19") (pin "2") (pinfunction "2_2") (pintype "passive"))
      (node (ref "U$4") (pin "9") (pinfunction "9_9") (pintype "passive"))
    )
    (net (code "58") (name "T5") (class "Default")
      (node (ref "74238") (pin "10") (pinfunction "Y5_10") (pintype "output"))
      (node (ref "R20") (pin "2") (pinfunction "2_2") (pintype "passive"))
      (node (ref "U$4") (pin "11") (pinfunction "11_11") (pintype "passive"))
    )
    (net (code "59") (name "T6") (class "Default")
      (node (ref "74238") (pin "9") (pinfunction "Y6_9") (pintype "output"))
      (node (ref "R21") (pin "2") (pinfunction "2_2") (pintype "passive"))
      (node (ref "U$4") (pin "13") (pinfunction "13_13") (pintype "passive"))
    )
    (net (code "60") (name "T7") (class "Default")
      (node (ref "74238") (pin "7") (pinfunction "Y7_7") (pintype "output"))
      (node (ref "R22") (pin "2") (pinfunction "2_2") (pintype "passive"))
      (node (ref "U$4") (pin "15") (pinfunction "15_15") (pintype "passive"))
    )
    (net (code "61") (name "TRIG1") (class "Default")
      (node (ref "MCP6004-TRIG") (pin "10") (pinfunction "+IN_10") (pintype "input"))
      (node (ref "U1") (pin "28") (pinfunction "PC5(ADC5/SCL)_28") (pintype "bidirectional"))
    )
    (net (code "62") (name "TRIG2") (class "Default")
      (node (ref "MCP6004-TRIG") (pin "5") (pinfunction "+IN_5") (pintype "input"))
      (node (ref "U1") (pin "30") (pinfunction "PD0(RXD)_30") (pintype "bidirectional"))
    )
    (net (code "63") (name "TRIG3") (class "Default")
      (node (ref "MCP6004-TRIG") (pin "3") (pinfunction "+IN_3") (pintype "input"))
      (node (ref "U1") (pin "31") (pinfunction "PD1(TXD)_31") (pintype "bidirectional"))
    )
    (net (code "64") (name "TRIG4") (class "Default")
      (node (ref "MCP6004-TRIG") (pin "12") (pinfunction "+IN_12") (pintype "input"))
      (node (ref "U1") (pin "1") (pinfunction "PD3(INT1)_1") (pintype "bidirectional"))
    )
    (net (code "65") (name "VOUTA") (class "Default")
      (node (ref "MCP4922") (pin "14") (pinfunction "VOUTA_14") (pintype "output"))
      (node (ref "MCP6004-V") (pin "10") (pinfunction "+IN_10") (pintype "input"))
    )
    (net (code "66") (name "VOUTB") (class "Default")
      (node (ref "MCP4922") (pin "10") (pinfunction "VOUTB_10") (pintype "output"))
      (node (ref "MCP6004-V") (pin "12") (pinfunction "+IN_12") (pintype "input"))
    )
    (net (code "67") (name "VOUTC") (class "Default")
      (node (ref "MCP4922-2") (pin "14") (pinfunction "VOUTA_14") (pintype "output"))
      (node (ref "MCP6004-V") (pin "3") (pinfunction "+IN_3") (pintype "input"))
    )
    (net (code "68") (name "VOUTD") (class "Default")
      (node (ref "MCP4922-2") (pin "10") (pinfunction "VOUTB_10") (pintype "output"))
      (node (ref "MCP6004-V") (pin "5") (pinfunction "+IN_5") (pintype "input"))
    )
    (net (code "69") (name "unconnected-(74151-1A-W-Pad6)") (class "Default")
      (node (ref "74151-1") (pin "6") (pinfunction "W_6") (pintype "output"))
    )
    (net (code "70") (name "unconnected-(75151-2A-W-Pad6)") (class "Default")
      (node (ref "75151-2") (pin "6") (pinfunction "W_6") (pintype "output"))
    )
    (net (code "71") (name "unconnected-(CLK_IN-PadNORM)") (class "Default")
      (node (ref "CLK_IN") (pin "NORM") (pinfunction "NORM_NORM") (pintype "passive"))
    )
    (net (code "72") (name "unconnected-(CV1-PadNORM)") (class "Default")
      (node (ref "CV1") (pin "NORM") (pinfunction "NORM_NORM") (pintype "passive"))
    )
    (net (code "73") (name "unconnected-(CV2-PadNORM)") (class "Default")
      (node (ref "CV2") (pin "NORM") (pinfunction "NORM_NORM") (pintype "passive"))
    )
    (net (code "74") (name "unconnected-(CV3-PadNORM)") (class "Default")
      (node (ref "CV3") (pin "NORM") (pinfunction "NORM_NORM") (pintype "passive"))
    )
    (net (code "75") (name "unconnected-(CV4-PadNORM)") (class "Default")
      (node (ref "CV4") (pin "NORM") (pinfunction "NORM_NORM") (pintype "passive"))
    )
    (net (code "76") (name "unconnected-(JP2-PadD+)") (class "Default")
      (node (ref "JP2") (pin "D+") (pinfunction "D+_D+") (pintype "bidirectional"))
    )
    (net (code "77") (name "unconnected-(JP2-PadD-)") (class "Default")
      (node (ref "JP2") (pin "D-") (pinfunction "D-_D-") (pintype "bidirectional"))
    )
    (net (code "78") (name "unconnected-(REF-NC-Pad3)") (class "Default")
      (node (ref "REF") (pin "3") (pinfunction "NC_3") (pintype "no_connect"))
    )
    (net (code "79") (name "unconnected-(TRIG1-PadNORM)") (class "Default")
      (node (ref "TRIG1") (pin "NORM") (pinfunction "NORM_NORM") (pintype "passive"))
    )
    (net (code "80") (name "unconnected-(TRIG2-PadNORM)") (class "Default")
      (node (ref "TRIG2") (pin "NORM") (pinfunction "NORM_NORM") (pintype "passive"))
    )
    (net (code "81") (name "unconnected-(TRIG3-PadNORM)") (class "Default")
      (node (ref "TRIG3") (pin "NORM") (pinfunction "NORM_NORM") (pintype "passive"))
    )
    (net (code "82") (name "unconnected-(TRIG4-PadNORM)") (class "Default")
      (node (ref "TRIG4") (pin "NORM") (pinfunction "NORM_NORM") (pintype "passive"))
    )
    (net (code "83") (name "unconnected-(U$4-Pad17)") (class "Default")
      (node (ref "U$4") (pin "17") (pinfunction "17_17") (pintype "passive"))
    )
    (net (code "84") (name "unconnected-(U$4-Pad19)") (class "Default")
      (node (ref "U$4") (pin "19") (pinfunction "19_19") (pintype "passive"))
    )
    (net (code "85") (name "unconnected-(U1-AREF-Pad20)") (class "Default")
      (node (ref "U1") (pin "20") (pinfunction "AREF_20") (pintype "bidirectional"))
    )
  )
)
